# Badge_Motor.net
KiCad netlist of a schematic drawn in EAGLE
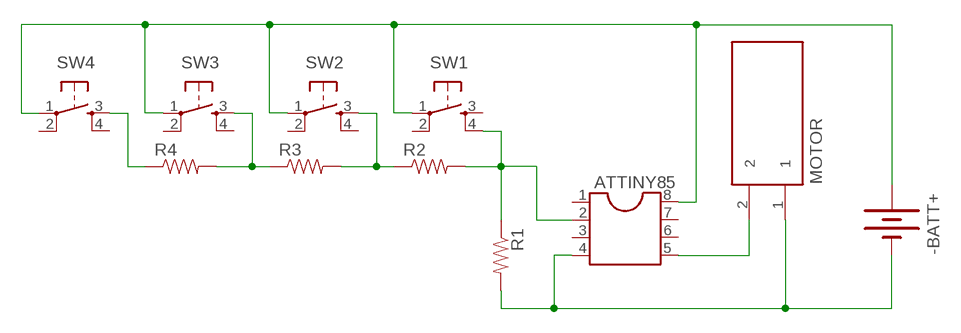
[diagram p0: schematic, sheet 1]

(export (version "E")
  (design (tool "Eeschema 10.0.6"))
  (components
    (comp (ref "-BATT+")
      (value "BATTERY245MM")
      (footprint "eagle-import:BATTCON_245MM")
      (libsource (lib "eagle-import") (part "BATTERY245MM"))
    )
    (comp (ref "ATTINY85")
      (value "DIL8S")
      (footprint "eagle-import:SOCKET-08")
      (libsource (lib "eagle-import") (part "DIL8S"))
    )
    (comp (ref "MOTOR")
      (value "VIB-MOTOR")
      (footprint "eagle-import:VIB-MOTOR")
      (libsource (lib "eagle-import") (part "VIB-MOTOR"))
    )
    (comp (ref "R1")
      (value "RESISTOR2010")
      (footprint "eagle-import:R2010")
      (libsource (lib "eagle-import") (part "RESISTOR2010"))
    )
    (comp (ref "R2")
      (value "RESISTOR2010")
      (footprint "eagle-import:R2010")
      (libsource (lib "eagle-import") (part "RESISTOR2010"))
    )
    (comp (ref "R3")
      (value "RESISTOR2010")
      (footprint "eagle-import:R2010")
      (libsource (lib "eagle-import") (part "RESISTOR2010"))
    )
    (comp (ref "R4")
      (value "RESISTOR2010")
      (footprint "eagle-import:R2010")
      (libsource (lib "eagle-import") (part "RESISTOR2010"))
    )
    (comp (ref "SW1")
      (value "TAC_SWITCHPTH")
      (footprint "eagle-import:TACTILE-PTH")
      (libsource (lib "eagle-import") (part "TAC_SWITCHPTH"))
    )
    (comp (ref "SW2")
      (value "TAC_SWITCHPTH")
      (footprint "eagle-import:TACTILE-PTH")
      (libsource (lib "eagle-import") (part "TAC_SWITCHPTH"))
    )
    (comp (ref "SW3")
      (value "TAC_SWITCHPTH")
      (footprint "eagle-import:TACTILE-PTH")
      (libsource (lib "eagle-import") (part "TAC_SWITCHPTH"))
    )
    (comp (ref "SW4")
      (value "TAC_SWITCHPTH")
      (footprint "eagle-import:TACTILE-PTH")
      (libsource (lib "eagle-import") (part "TAC_SWITCHPTH"))
    )
  )
  (nets
    (net (code "1") (name "Net-(-BATT+-+)") (class "Default")
      (node (ref "-BATT+") (pin "1") (pinfunction "+_1") (pintype "power_in"))
      (node (ref "ATTINY85") (pin "8") (pinfunction "8_8") (pintype "passive"))
      (node (ref "SW1") (pin "1") (pinfunction "1_1") (pintype "passive"))
      (node (ref "SW2") (pin "1") (pinfunction "1_1") (pintype "passive"))
      (node (ref "SW3") (pin "1") (pinfunction "1_1") (pintype "passive"))
      (node (ref "SW4") (pin "1") (pinfunction "1_1") (pintype "passive"))
    )
    (net (code "2") (name "Net-(-BATT+--)") (class "Default")
      (node (ref "-BATT+") (pin "2") (pinfunction "-_2") (pintype "power_in"))
      (node (ref "ATTINY85") (pin "4") (pinfunction "4_4") (pintype "passive"))
      (node (ref "MOTOR") (pin "1") (pinfunction "1_1") (pintype "bidirectional"))
      (node (ref "R1") (pin "2") (pinfunction "2_2") (pintype "passive"))
    )
    (net (code "3") (name "Net-(ATTINY85-Pad2)") (class "Default")
      (node (ref "ATTINY85") (pin "2") (pinfunction "2_2") (pintype "passive"))
      (node (ref "R1") (pin "1") (pinfunction "1_1") (pintype "passive"))
      (node (ref "R2") (pin "2") (pinfunction "2_2") (pintype "passive"))
      (node (ref "SW1") (pin "4") (pinfunction "4_4") (pintype "passive"))
    )
    (net (code "4") (name "Net-(ATTINY85-Pad5)") (class "Default")
      (node (ref "ATTINY85") (pin "5") (pinfunction "5_5") (pintype "passive"))
      (node (ref "MOTOR") (pin "2") (pinfunction "2_2") (pintype "bidirectional"))
    )
    (net (code "5") (name "Net-(R2-Pad1)") (class "Default")
      (node (ref "R2") (pin "1") (pinfunction "1_1") (pintype "passive"))
      (node (ref "R3") (pin "2") (pinfunction "2_2") (pintype "passive"))
      (node (ref "SW2") (pin "3") (pinfunction "3_3") (pintype "passive"))
    )
    (net (code "6") (name "Net-(R3-Pad1)") (class "Default")
      (node (ref "R3") (pin "1") (pinfunction "1_1") (pintype "passive"))
      (node (ref "R4") (pin "2") (pinfunction "2_2") (pintype "passive"))
      (node (ref "SW3") (pin "3") (pinfunction "3_3") (pintype "passive"))
    )
    (net (code "7") (name "Net-(R4-Pad1)") (class "Default")
      (node (ref "R4") (pin "1") (pinfunction "1_1") (pintype "passive"))
      (node (ref "SW4") (pin "3") (pinfunction "3_3") (pintype "passive"))
    )
    (net (code "8") (name "unconnected-(ATTINY85-Pad1)") (class "Default")
      (node (ref "ATTINY85") (pin "1") (pinfunction "1_1") (pintype "passive"))
    )
    (net (code "9") (name "unconnected-(ATTINY85-Pad3)") (class "Default")
      (node (ref "ATTINY85") (pin "3") (pinfunction "3_3") (pintype "passive"))
    )
    (net (code "10") (name "unconnected-(ATTINY85-Pad6)") (class "Default")
      (node (ref "ATTINY85") (pin "6") (pinfunction "6_6") (pintype "passive"))
    )
    (net (code "11") (name "unconnected-(ATTINY85-Pad7)") (class "Default")
      (node (ref "ATTINY85") (pin "7") (pinfunction "7_7") (pintype "passive"))
    )
    (net (code "12") (name "unconnected-(SW1-Pad2)") (class "Default")
      (node (ref "SW1") (pin "2") (pinfunction "2_2") (pintype "passive"))
    )
    (net (code "13") (name "unconnected-(SW1-Pad3)") (class "Default")
      (node (ref "SW1") (pin "3") (pinfunction "3_3") (pintype "passive"))
    )
    (net (code "14") (name "unconnected-(SW2-Pad2)") (class "Default")
      (node (ref "SW2") (pin "2") (pinfunction "2_2") (pintype "passive"))
    )
    (net (code "15") (name "unconnected-(SW2-Pad4)") (class "Default")
      (node (ref "SW2") (pin "4") (pinfunction "4_4") (pintype "passive"))
    )
    (net (code "16") (name "unconnected-(SW3-Pad2)") (class "Default")
      (node (ref "SW3") (pin "2") (pinfunction "2_2") (pintype "passive"))
    )
    (net (code "17") (name "unconnected-(SW3-Pad4)") (class "Default")
      (node (ref "SW3") (pin "4") (pinfunction "4_4") (pintype "passive"))
    )
    (net (code "18") (name "unconnected-(SW4-Pad2)") (class "Default")
      (node (ref "SW4") (pin "2") (pinfunction "2_2") (pintype "passive"))
    )
    (net (code "19") (name "unconnected-(SW4-Pad4)") (class "Default")
      (node (ref "SW4") (pin "4") (pinfunction "4_4") (pintype "passive"))
    )
  )
)
